# DC_Measure.net
KiCad netlist of a schematic drawn in Altium Designer
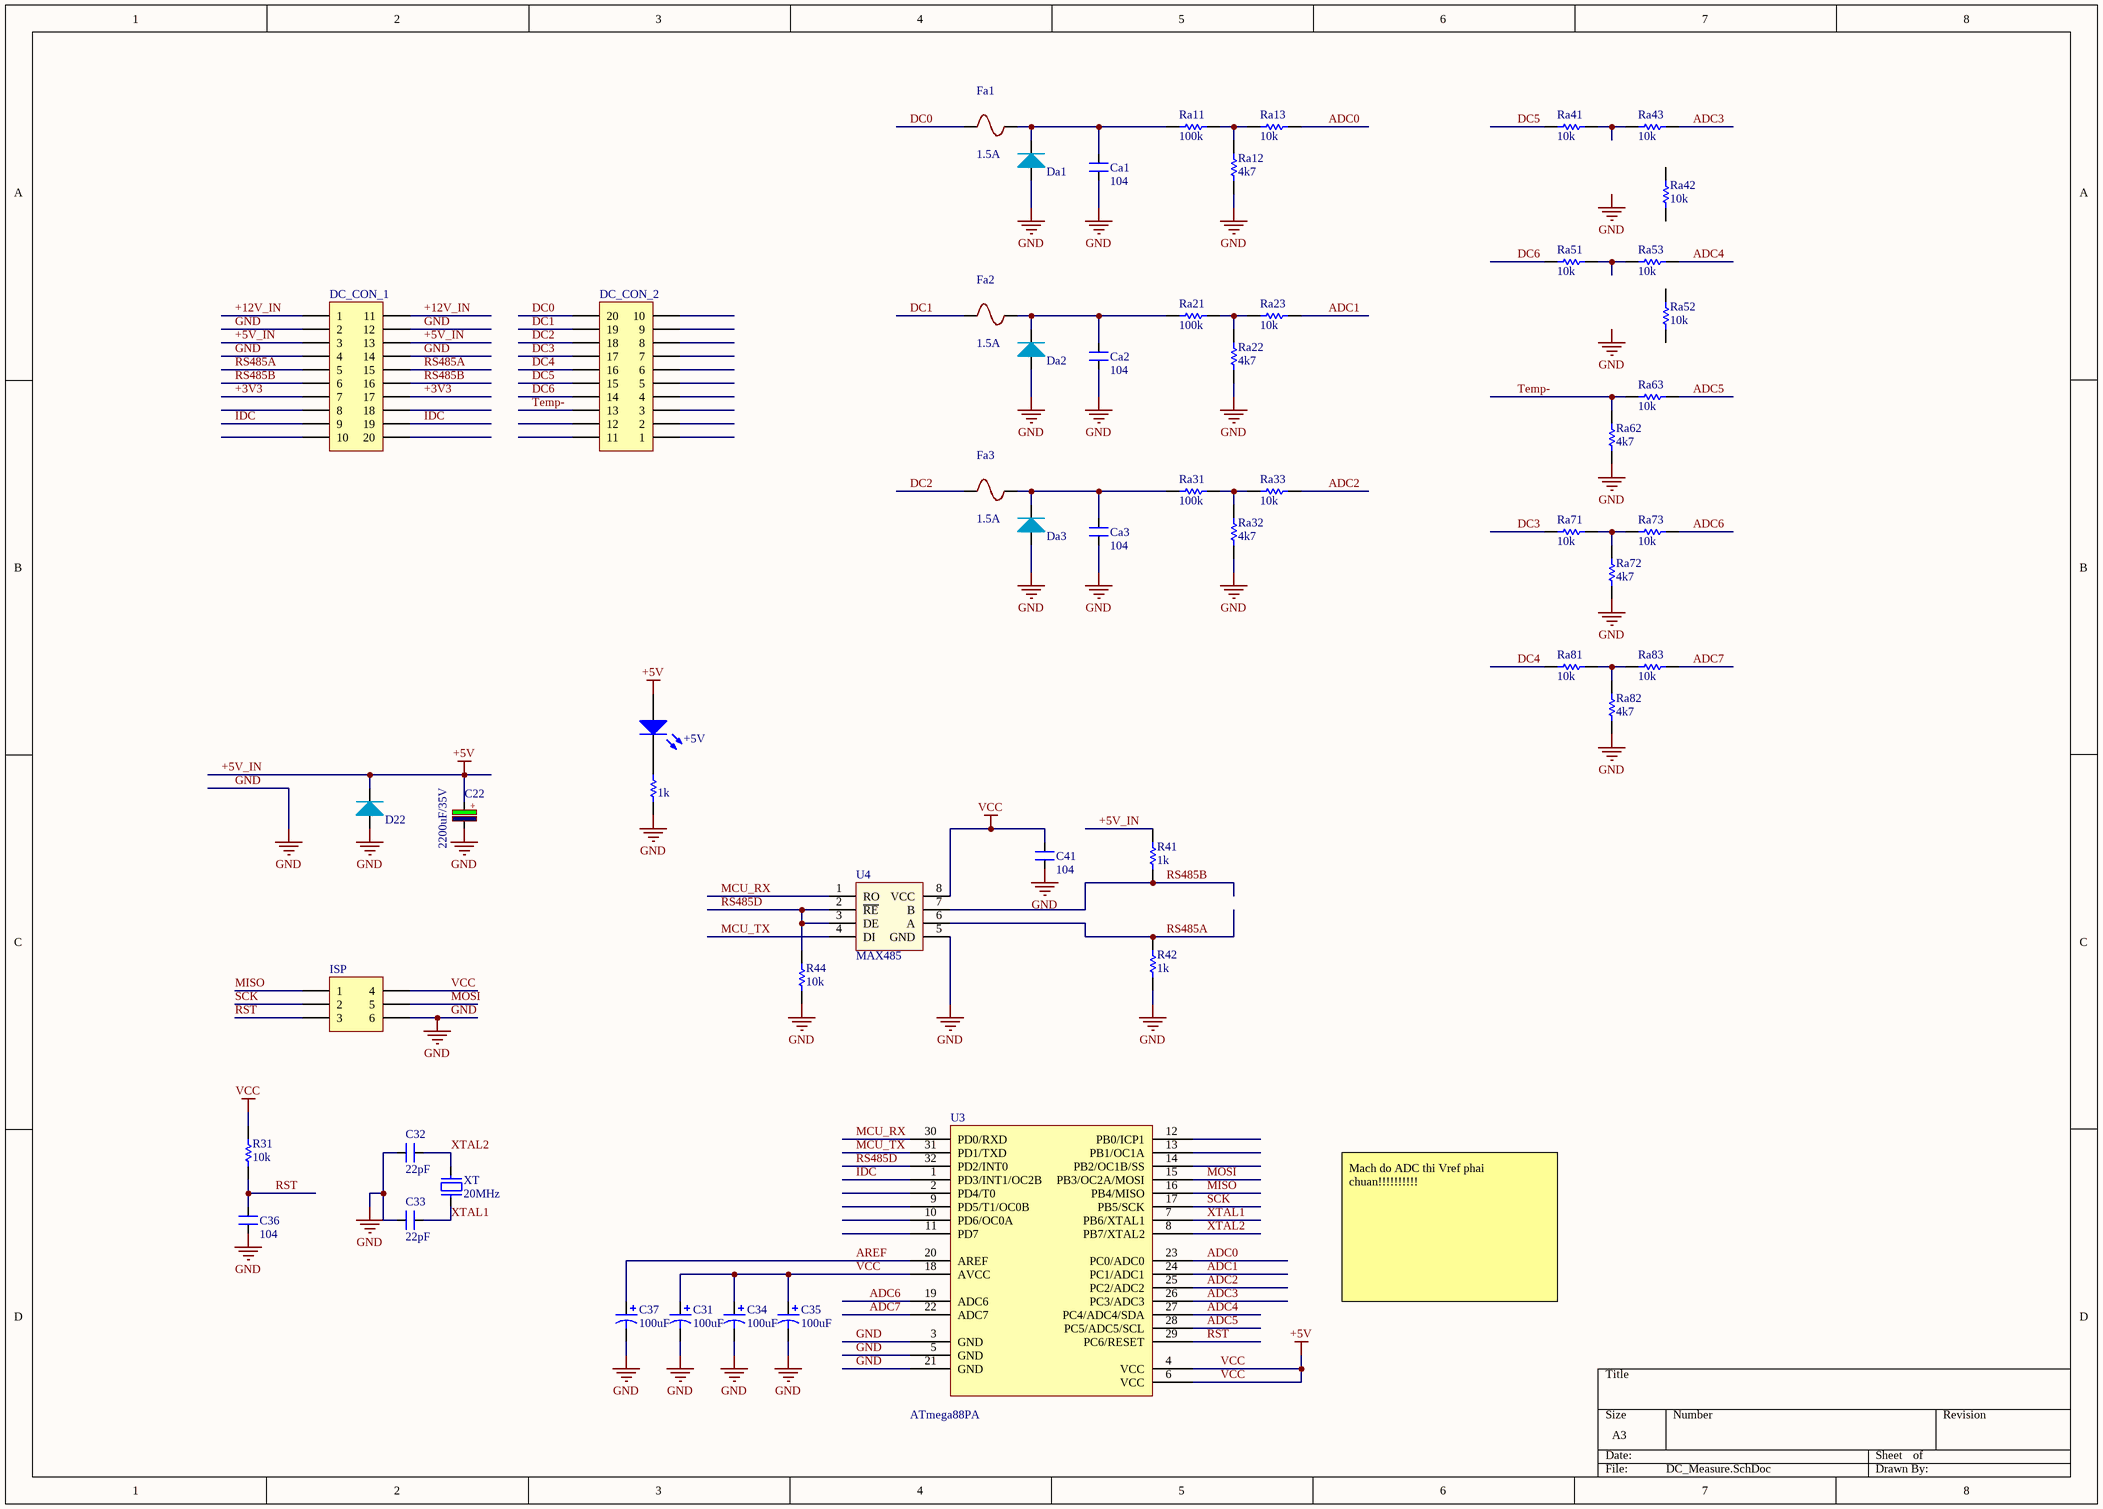
[diagram p0: DC_Measure.SchDoc]

(export (version "E")
  (design (tool "Eeschema 10.0.6"))
  (components
    (comp (ref "+5V") (value "Led") (footprint "LED 5mm RED") (libsource (lib "Tuan") (part "Led")))
    (comp (ref "C22")
      (value "2200uF/35V")
      (footprint "PBL - SMD Packages:CAP_ELEC_SIZE_G")
      (description "Cap 1000uF/16V - 220uF/50V")
      (libsource (lib "heromap") (part "CP4"))
    )
    (comp (ref "C31")
      (value "100uF")
      (footprint "CAPC2012N_F")
      (fields (field (name "Comment") "Cap"))
      (libsource (lib "Tuan") (part "Cap"))
    )
    (comp (ref "C32")
      (value "22pF")
      (footprint "CAPC1608N")
      (fields (field (name "Comment") "CAP NP"))
      (libsource (lib "Tuan") (part "CAP NP"))
    )
    (comp (ref "C33")
      (value "22pF")
      (footprint "CAPC1608N")
      (fields (field (name "Comment") "CAP NP"))
      (libsource (lib "Tuan") (part "CAP NP"))
    )
    (comp (ref "C34")
      (value "100uF")
      (footprint "CAPC2012N_F")
      (fields (field (name "Comment") "Cap"))
      (libsource (lib "Tuan") (part "Cap"))
    )
    (comp (ref "C35")
      (value "100uF")
      (footprint "CAPC2012N_F")
      (fields (field (name "Comment") "Cap"))
      (libsource (lib "Tuan") (part "Cap"))
    )
    (comp (ref "C36")
      (value "104")
      (footprint "CAPC1608N")
      (fields (field (name "Comment") "CAP NP"))
      (libsource (lib "Tuan") (part "CAP NP"))
    )
    (comp (ref "C37")
      (value "100uF")
      (footprint "CAPC2012N_F")
      (fields (field (name "Comment") "Cap"))
      (libsource (lib "Tuan") (part "Cap"))
    )
    (comp (ref "C41")
      (value "104")
      (footprint "CAPC2012N_F")
      (fields (field (name "Comment") "100nF/104"))
      (libsource (lib "Tuan") (part "CAP NP"))
    )
    (comp (ref "Ca1")
      (value "104")
      (footprint "CAPC2012N_F")
      (fields (field (name "Comment") "CAP NP"))
      (libsource (lib "Tuan") (part "CAP NP"))
    )
    (comp (ref "Ca2")
      (value "104")
      (footprint "CAPC2012N_F")
      (fields (field (name "Comment") "CAP NP"))
      (libsource (lib "Tuan") (part "CAP NP"))
    )
    (comp (ref "Ca3")
      (value "104")
      (footprint "CAPC2012N_F")
      (fields (field (name "Comment") "CAP NP"))
      (libsource (lib "Tuan") (part "CAP NP"))
    )
    (comp (ref "D22") (value "Diode") (footprint "DO-214AC") (libsource (lib "Tuan") (part "Diode")))
    (comp (ref "Da1") (value "Diode") (footprint "DO-214AC") (libsource (lib "Tuan") (part "Diode")))
    (comp (ref "Da2") (value "Diode") (footprint "DO-214AC") (libsource (lib "Tuan") (part "Diode")))
    (comp (ref "Da3") (value "Diode") (footprint "DO-214AC") (libsource (lib "Tuan") (part "Diode")))
    (comp (ref "DC_CON_1")
      (value "Header 10X2A")
      (footprint "OMC10")
      (description "Header, 10-Pin, Dual row")
      (fields (field (name "PUBLISHER") "Altium Limited"))
      (libsource (lib "") (part "Header 10X2A_1"))
    )
    (comp (ref "DC_CON_2")
      (value "Header 10X2A")
      (footprint "OMC10")
      (description "Header, 10-Pin, Dual row")
      (fields (field (name "PUBLISHER") "Altium Limited"))
      (libsource (lib "Miscellaneous Connectors") (part "Header 10X2A"))
    )
    (comp (ref "Fa1") (value "1.5A") (footprint "SMD 1206") (libsource (lib "Tuan") (part "Fuse")))
    (comp (ref "Fa2") (value "1.5A") (footprint "SMD 1206") (libsource (lib "Tuan") (part "Fuse")))
    (comp (ref "Fa3") (value "1.5A") (footprint "SMD 1206") (libsource (lib "Tuan") (part "Fuse")))
    (comp (ref "ISP")
      (value "Header 3X2A")
      (footprint "HDR2X3_CEN")
      (description "Header, 3-Pin, Dual row")
      (fields (field (name "PUBLISHER") "Altium Limited"))
      (libsource (lib "Miscellaneous Connectors") (part "Header 3X2A"))
    )
    (comp (ref "R22")
      (value "1k")
      (footprint "RESC2012N_F")
      (fields (field (name "Comment") "Res_0805_1k"))
      (libsource (lib "Tuan") (part "Res"))
    )
    (comp (ref "R31")
      (value "10k")
      (footprint "RESC1608N_ZERO")
      (fields (field (name "Comment") "Res"))
      (libsource (lib "Tuan") (part "Res"))
    )
    (comp (ref "R41")
      (value "1k")
      (footprint "RESC1608N_ZERO")
      (description "Tro dan")
      (libsource (lib "GPS_Clock_v12") (part "Res"))
    )
    (comp (ref "R42")
      (value "1k")
      (footprint "RESC1608N_ZERO")
      (description "Tro dan")
      (libsource (lib "GPS_Clock_v12") (part "Res"))
    )
    (comp (ref "R44")
      (value "10k")
      (footprint "RESC1608N_ZERO")
      (description "Tro dan")
      (fields (field (name "Comment") "330R"))
      (libsource (lib "GPS_Clock_v12") (part "Res"))
    )
    (comp (ref "Ra11")
      (value "100k")
      (footprint "RESC2012N_F")
      (fields (field (name "Comment") "Res"))
      (libsource (lib "Tuan") (part "Res"))
    )
    (comp (ref "Ra12")
      (value "4k7")
      (footprint "RESC2012N_F")
      (fields (field (name "Comment") "Res"))
      (libsource (lib "Tuan") (part "Res"))
    )
    (comp (ref "Ra13")
      (value "10k")
      (footprint "RESC2012N_F")
      (fields (field (name "Comment") "Res"))
      (libsource (lib "Tuan") (part "Res"))
    )
    (comp (ref "Ra21")
      (value "100k")
      (footprint "RESC2012N_F")
      (fields (field (name "Comment") "Res"))
      (libsource (lib "Tuan") (part "Res"))
    )
    (comp (ref "Ra22")
      (value "4k7")
      (footprint "RESC2012N_F")
      (fields (field (name "Comment") "Res"))
      (libsource (lib "Tuan") (part "Res"))
    )
    (comp (ref "Ra23")
      (value "10k")
      (footprint "RESC2012N_F")
      (fields (field (name "Comment") "Res"))
      (libsource (lib "Tuan") (part "Res"))
    )
    (comp (ref "Ra31")
      (value "100k")
      (footprint "RESC2012N_F")
      (fields (field (name "Comment") "Res"))
      (libsource (lib "Tuan") (part "Res"))
    )
    (comp (ref "Ra32")
      (value "4k7")
      (footprint "RESC2012N_F")
      (fields (field (name "Comment") "Res"))
      (libsource (lib "Tuan") (part "Res"))
    )
    (comp (ref "Ra33")
      (value "10k")
      (footprint "RESC2012N_F")
      (fields (field (name "Comment") "Res"))
      (libsource (lib "Tuan") (part "Res"))
    )
    (comp (ref "Ra41")
      (value "10k")
      (footprint "RESC2012N_F")
      (fields (field (name "Comment") "Res"))
      (libsource (lib "Tuan") (part "Res"))
    )
    (comp (ref "Ra42")
      (value "10k")
      (footprint "RESC2012N_F")
      (fields (field (name "Comment") "Res"))
      (libsource (lib "Tuan") (part "Res"))
    )
    (comp (ref "Ra43")
      (value "10k")
      (footprint "RESC2012N_F")
      (fields (field (name "Comment") "Res"))
      (libsource (lib "Tuan") (part "Res"))
    )
    (comp (ref "Ra51")
      (value "10k")
      (footprint "RESC2012N_F")
      (fields (field (name "Comment") "Res"))
      (libsource (lib "Tuan") (part "Res"))
    )
    (comp (ref "Ra52")
      (value "10k")
      (footprint "RESC2012N_F")
      (fields (field (name "Comment") "Res"))
      (libsource (lib "Tuan") (part "Res"))
    )
    (comp (ref "Ra53")
      (value "10k")
      (footprint "RESC2012N_F")
      (fields (field (name "Comment") "Res"))
      (libsource (lib "Tuan") (part "Res"))
    )
    (comp (ref "Ra62")
      (value "4k7")
      (footprint "RESC2012N_F")
      (fields (field (name "Comment") "Res"))
      (libsource (lib "Tuan") (part "Res"))
    )
    (comp (ref "Ra63")
      (value "10k")
      (footprint "RESC2012N_F")
      (fields (field (name "Comment") "Res"))
      (libsource (lib "Tuan") (part "Res"))
    )
    (comp (ref "Ra71")
      (value "10k")
      (footprint "RESC2012N_F")
      (fields (field (name "Comment") "Res"))
      (libsource (lib "Tuan") (part "Res"))
    )
    (comp (ref "Ra72")
      (value "4k7")
      (footprint "RESC2012N_F")
      (fields (field (name "Comment") "Res"))
      (libsource (lib "Tuan") (part "Res"))
    )
    (comp (ref "Ra73")
      (value "10k")
      (footprint "RESC2012N_F")
      (fields (field (name "Comment") "Res"))
      (libsource (lib "Tuan") (part "Res"))
    )
    (comp (ref "Ra81")
      (value "10k")
      (footprint "RESC2012N_F")
      (fields (field (name "Comment") "Res"))
      (libsource (lib "Tuan") (part "Res"))
    )
    (comp (ref "Ra82")
      (value "4k7")
      (footprint "RESC2012N_F")
      (fields (field (name "Comment") "Res"))
      (libsource (lib "Tuan") (part "Res"))
    )
    (comp (ref "Ra83")
      (value "10k")
      (footprint "RESC2012N_F")
      (fields (field (name "Comment") "Res"))
      (libsource (lib "Tuan") (part "Res"))
    )
    (comp (ref "U3")
      (value "ATmega88PA")
      (footprint "32PIN")
      (description "ATmega48/168/328")
      (libsource (lib "Tuan") (part "ATmega48/168/328"))
    )
    (comp (ref "U4")
      (value "MAX485")
      (footprint "SO-8")
      (description "RS232 - RS485 (Same sn75176)")
      (libsource (lib "heromap") (part "MAX485"))
    )
    (comp (ref "XT") (value "20MHz") (footprint "XT2") (libsource (lib "Tuan") (part "Crystal")))
  )
  (nets
    (net (code "1") (name "+5V") (class "Default")
      (node (ref "+5V") (pin "1") (pinfunction "A_1") (pintype "passive"))
      (node (ref "C22") (pin "1") (pinfunction "1_1") (pintype "passive"))
      (node (ref "C31") (pin "1") (pinfunction "1_1") (pintype "passive"))
      (node (ref "C34") (pin "1") (pinfunction "1_1") (pintype "passive"))
      (node (ref "C35") (pin "1") (pinfunction "1_1") (pintype "passive"))
      (node (ref "C41") (pin "2") (pinfunction "2_2") (pintype "passive"))
      (node (ref "D22") (pin "2") (pinfunction "K_2") (pintype "passive"))
      (node (ref "DC_CON_1") (pin "13") (pinfunction "13_13") (pintype "passive"))
      (node (ref "DC_CON_1") (pin "3") (pinfunction "3_3") (pintype "passive"))
      (node (ref "ISP") (pin "4") (pinfunction "4_4") (pintype "passive"))
      (node (ref "R31") (pin "2") (pinfunction "2_2") (pintype "passive"))
      (node (ref "R41") (pin "2") (pinfunction "2_2") (pintype "passive"))
      (node (ref "U3") (pin "18") (pinfunction "AVCC_18") (pintype "passive"))
      (node (ref "U3") (pin "4") (pinfunction "VCC_4") (pintype "passive"))
      (node (ref "U3") (pin "6") (pinfunction "VCC_6") (pintype "passive"))
      (node (ref "U4") (pin "8") (pinfunction "VCC_8") (pintype "passive"))
    )
    (net (code "2") (name "/+3V3") (class "Default")
      (node (ref "DC_CON_1") (pin "17") (pinfunction "17_17") (pintype "passive"))
      (node (ref "DC_CON_1") (pin "7") (pinfunction "7_7") (pintype "passive"))
    )
    (net (code "3") (name "/+12V_IN") (class "Default")
      (node (ref "DC_CON_1") (pin "1") (pinfunction "1_1") (pintype "passive"))
      (node (ref "DC_CON_1") (pin "11") (pinfunction "11_11") (pintype "passive"))
    )
    (net (code "4") (name "/ADC0") (class "Default")
      (node (ref "Ra13") (pin "1") (pinfunction "1_1") (pintype "passive"))
      (node (ref "U3") (pin "23") (pinfunction "PC0/ADC0_23") (pintype "passive"))
    )
    (net (code "5") (name "/ADC1") (class "Default")
      (node (ref "Ra23") (pin "2") (pinfunction "2_2") (pintype "passive"))
      (node (ref "U3") (pin "24") (pinfunction "PC1/ADC1_24") (pintype "passive"))
    )
    (net (code "6") (name "/ADC2") (class "Default")
      (node (ref "Ra33") (pin "1") (pinfunction "1_1") (pintype "passive"))
      (node (ref "U3") (pin "25") (pinfunction "PC2/ADC2_25") (pintype "passive"))
    )
    (net (code "7") (name "/ADC3") (class "Default")
      (node (ref "Ra43") (pin "1") (pinfunction "1_1") (pintype "passive"))
      (node (ref "U3") (pin "26") (pinfunction "PC3/ADC3_26") (pintype "passive"))
    )
    (net (code "8") (name "/ADC4") (class "Default")
      (node (ref "Ra53") (pin "2") (pinfunction "2_2") (pintype "passive"))
      (node (ref "U3") (pin "27") (pinfunction "PC4/ADC4/SDA_27") (pintype "passive"))
    )
    (net (code "9") (name "/ADC5") (class "Default")
      (node (ref "Ra63") (pin "1") (pinfunction "1_1") (pintype "passive"))
      (node (ref "U3") (pin "28") (pinfunction "PC5/ADC5/SCL_28") (pintype "passive"))
    )
    (net (code "10") (name "/ADC6") (class "Default")
      (node (ref "Ra73") (pin "2") (pinfunction "2_2") (pintype "passive"))
      (node (ref "U3") (pin "19") (pinfunction "ADC6_19") (pintype "passive"))
    )
    (net (code "11") (name "/ADC7") (class "Default")
      (node (ref "Ra83") (pin "2") (pinfunction "2_2") (pintype "passive"))
      (node (ref "U3") (pin "22") (pinfunction "ADC7_22") (pintype "passive"))
    )
    (net (code "12") (name "/AREF") (class "Default")
      (node (ref "C37") (pin "1") (pinfunction "1_1") (pintype "passive"))
      (node (ref "U3") (pin "20") (pinfunction "AREF_20") (pintype "passive"))
    )
    (net (code "13") (name "/DC0") (class "Default")
      (node (ref "DC_CON_2") (pin "20") (pinfunction "20_20") (pintype "passive"))
      (node (ref "Fa1") (pin "1") (pinfunction "1_1") (pintype "passive"))
    )
    (net (code "14") (name "/DC1") (class "Default")
      (node (ref "DC_CON_2") (pin "19") (pinfunction "19_19") (pintype "passive"))
      (node (ref "Fa2") (pin "1") (pinfunction "1_1") (pintype "passive"))
    )
    (net (code "15") (name "/DC2") (class "Default")
      (node (ref "DC_CON_2") (pin "18") (pinfunction "18_18") (pintype "passive"))
      (node (ref "Fa3") (pin "1") (pinfunction "1_1") (pintype "passive"))
    )
    (net (code "16") (name "/DC3") (class "Default")
      (node (ref "DC_CON_2") (pin "17") (pinfunction "17_17") (pintype "passive"))
      (node (ref "Ra71") (pin "2") (pinfunction "2_2") (pintype "passive"))
    )
    (net (code "17") (name "/DC4") (class "Default")
      (node (ref "DC_CON_2") (pin "16") (pinfunction "16_16") (pintype "passive"))
      (node (ref "Ra81") (pin "2") (pinfunction "2_2") (pintype "passive"))
    )
    (net (code "18") (name "/DC5") (class "Default")
      (node (ref "DC_CON_2") (pin "15") (pinfunction "15_15") (pintype "passive"))
      (node (ref "Ra41") (pin "1") (pinfunction "1_1") (pintype "passive"))
    )
    (net (code "19") (name "/DC6") (class "Default")
      (node (ref "DC_CON_2") (pin "14") (pinfunction "14_14") (pintype "passive"))
      (node (ref "Ra51") (pin "2") (pinfunction "2_2") (pintype "passive"))
    )
    (net (code "20") (name "/IDC") (class "Default")
      (node (ref "DC_CON_1") (pin "19") (pinfunction "19_19") (pintype "passive"))
      (node (ref "DC_CON_1") (pin "9") (pinfunction "9_9") (pintype "passive"))
      (node (ref "U3") (pin "1") (pinfunction "PD3/INT1/OC2B_1") (pintype "passive"))
    )
    (net (code "21") (name "/MCU_RX") (class "Default")
      (node (ref "U3") (pin "30") (pinfunction "PD0/RXD_30") (pintype "passive"))
      (node (ref "U4") (pin "1") (pinfunction "RO_1") (pintype "passive"))
    )
    (net (code "22") (name "/MCU_TX") (class "Default")
      (node (ref "U3") (pin "31") (pinfunction "PD1/TXD_31") (pintype "passive"))
      (node (ref "U4") (pin "4") (pinfunction "DI_4") (pintype "passive"))
    )
    (net (code "23") (name "/MISO") (class "Default")
      (node (ref "ISP") (pin "1") (pinfunction "1_1") (pintype "passive"))
      (node (ref "U3") (pin "16") (pinfunction "PB4/MISO_16") (pintype "passive"))
    )
    (net (code "24") (name "/MOSI") (class "Default")
      (node (ref "ISP") (pin "5") (pinfunction "5_5") (pintype "passive"))
      (node (ref "U3") (pin "15") (pinfunction "PB3/OC2A/MOSI_15") (pintype "passive"))
    )
    (net (code "25") (name "/RS485A") (class "Default")
      (node (ref "DC_CON_1") (pin "15") (pinfunction "15_15") (pintype "passive"))
      (node (ref "DC_CON_1") (pin "5") (pinfunction "5_5") (pintype "passive"))
      (node (ref "R42") (pin "2") (pinfunction "2_2") (pintype "passive"))
      (node (ref "U4") (pin "6") (pinfunction "A_6") (pintype "passive"))
    )
    (net (code "26") (name "/RS485B") (class "Default")
      (node (ref "DC_CON_1") (pin "16") (pinfunction "16_16") (pintype "passive"))
      (node (ref "DC_CON_1") (pin "6") (pinfunction "6_6") (pintype "passive"))
      (node (ref "R41") (pin "1") (pinfunction "1_1") (pintype "passive"))
      (node (ref "U4") (pin "7") (pinfunction "B_7") (pintype "passive"))
    )
    (net (code "27") (name "/RS485D") (class "Default")
      (node (ref "R44") (pin "2") (pinfunction "2_2") (pintype "passive"))
      (node (ref "U3") (pin "32") (pinfunction "PD2/INT0_32") (pintype "passive"))
      (node (ref "U4") (pin "2") (pinfunction "~{RE}_2") (pintype "passive"))
      (node (ref "U4") (pin "3") (pinfunction "DE_3") (pintype "passive"))
    )
    (net (code "28") (name "/RST") (class "Default")
      (node (ref "C36") (pin "2") (pinfunction "2_2") (pintype "passive"))
      (node (ref "ISP") (pin "3") (pinfunction "3_3") (pintype "passive"))
      (node (ref "R31") (pin "1") (pinfunction "1_1") (pintype "passive"))
      (node (ref "U3") (pin "29") (pinfunction "PC6/RESET_29") (pintype "passive"))
    )
    (net (code "29") (name "/SCK") (class "Default")
      (node (ref "ISP") (pin "2") (pinfunction "2_2") (pintype "passive"))
      (node (ref "U3") (pin "17") (pinfunction "PB5/SCK_17") (pintype "passive"))
    )
    (net (code "30") (name "/Temp-") (class "Default")
      (node (ref "DC_CON_2") (pin "13") (pinfunction "13_13") (pintype "passive"))
      (node (ref "Ra62") (pin "2") (pinfunction "2_2") (pintype "passive"))
      (node (ref "Ra63") (pin "2") (pinfunction "2_2") (pintype "passive"))
    )
    (net (code "31") (name "/XTAL1") (class "Default")
      (node (ref "C33") (pin "1") (pinfunction "1_1") (pintype "passive"))
      (node (ref "U3") (pin "7") (pinfunction "PB6/XTAL1_7") (pintype "passive"))
      (node (ref "XT") (pin "1") (pinfunction "1_1") (pintype "passive"))
    )
    (net (code "32") (name "/XTAL2") (class "Default")
      (node (ref "C32") (pin "1") (pinfunction "1_1") (pintype "passive"))
      (node (ref "U3") (pin "8") (pinfunction "PB7/XTAL2_8") (pintype "passive"))
      (node (ref "XT") (pin "2") (pinfunction "2_2") (pintype "passive"))
    )
    (net (code "33") (name "GND") (class "Default")
      (node (ref "C22") (pin "2") (pinfunction "2_2") (pintype "passive"))
      (node (ref "C31") (pin "2") (pinfunction "2_2") (pintype "passive"))
      (node (ref "C32") (pin "2") (pinfunction "2_2") (pintype "passive"))
      (node (ref "C33") (pin "2") (pinfunction "2_2") (pintype "passive"))
      (node (ref "C34") (pin "2") (pinfunction "2_2") (pintype "passive"))
      (node (ref "C35") (pin "2") (pinfunction "2_2") (pintype "passive"))
      (node (ref "C36") (pin "1") (pinfunction "1_1") (pintype "passive"))
      (node (ref "C37") (pin "2") (pinfunction "2_2") (pintype "passive"))
      (node (ref "C41") (pin "1") (pinfunction "1_1") (pintype "passive"))
      (node (ref "Ca1") (pin "1") (pinfunction "1_1") (pintype "passive"))
      (node (ref "Ca2") (pin "1") (pinfunction "1_1") (pintype "passive"))
      (node (ref "Ca3") (pin "1") (pinfunction "1_1") (pintype "passive"))
      (node (ref "D22") (pin "1") (pinfunction "A_1") (pintype "passive"))
      (node (ref "DC_CON_1") (pin "12") (pinfunction "12_12") (pintype "passive"))
      (node (ref "DC_CON_1") (pin "14") (pinfunction "14_14") (pintype "passive"))
      (node (ref "DC_CON_1") (pin "2") (pinfunction "2_2") (pintype "passive"))
      (node (ref "DC_CON_1") (pin "4") (pinfunction "4_4") (pintype "passive"))
      (node (ref "Da1") (pin "1") (pinfunction "A_1") (pintype "passive"))
      (node (ref "Da2") (pin "1") (pinfunction "A_1") (pintype "passive"))
      (node (ref "Da3") (pin "1") (pinfunction "A_1") (pintype "passive"))
      (node (ref "ISP") (pin "6") (pinfunction "6_6") (pintype "passive"))
      (node (ref "R22") (pin "2") (pinfunction "2_2") (pintype "passive"))
      (node (ref "R42") (pin "1") (pinfunction "1_1") (pintype "passive"))
      (node (ref "R44") (pin "1") (pinfunction "1_1") (pintype "passive"))
      (node (ref "Ra12") (pin "1") (pinfunction "1_1") (pintype "passive"))
      (node (ref "Ra22") (pin "2") (pinfunction "2_2") (pintype "passive"))
      (node (ref "Ra32") (pin "1") (pinfunction "1_1") (pintype "passive"))
      (node (ref "Ra62") (pin "1") (pinfunction "1_1") (pintype "passive"))
      (node (ref "Ra72") (pin "2") (pinfunction "2_2") (pintype "passive"))
      (node (ref "Ra82") (pin "2") (pinfunction "2_2") (pintype "passive"))
      (node (ref "U3") (pin "21") (pinfunction "GND_21") (pintype "power_in"))
      (node (ref "U3") (pin "3") (pinfunction "GND_3") (pintype "power_in"))
      (node (ref "U3") (pin "5") (pinfunction "GND_5") (pintype "power_in"))
      (node (ref "U4") (pin "5") (pinfunction "GND_5") (pintype "passive"))
    )
    (net (code "34") (name "Net-(+5V-K)") (class "Default")
      (node (ref "+5V") (pin "2") (pinfunction "K_2") (pintype "passive"))
      (node (ref "R22") (pin "1") (pinfunction "1_1") (pintype "passive"))
    )
    (net (code "35") (name "Net-(Da1-K)") (class "Default")
      (node (ref "Ca1") (pin "2") (pinfunction "2_2") (pintype "passive"))
      (node (ref "Da1") (pin "2") (pinfunction "K_2") (pintype "passive"))
      (node (ref "Fa1") (pin "2") (pinfunction "2_2") (pintype "passive"))
      (node (ref "Ra11") (pin "1") (pinfunction "1_1") (pintype "passive"))
    )
    (net (code "36") (name "Net-(Da2-K)") (class "Default")
      (node (ref "Ca2") (pin "2") (pinfunction "2_2") (pintype "passive"))
      (node (ref "Da2") (pin "2") (pinfunction "K_2") (pintype "passive"))
      (node (ref "Fa2") (pin "2") (pinfunction "2_2") (pintype "passive"))
      (node (ref "Ra21") (pin "2") (pinfunction "2_2") (pintype "passive"))
    )
    (net (code "37") (name "Net-(Da3-K)") (class "Default")
      (node (ref "Ca3") (pin "2") (pinfunction "2_2") (pintype "passive"))
      (node (ref "Da3") (pin "2") (pinfunction "K_2") (pintype "passive"))
      (node (ref "Fa3") (pin "2") (pinfunction "2_2") (pintype "passive"))
      (node (ref "Ra31") (pin "1") (pinfunction "1_1") (pintype "passive"))
    )
    (net (code "38") (name "Net-(Ra11-Pad2)") (class "Default")
      (node (ref "Ra11") (pin "2") (pinfunction "2_2") (pintype "passive"))
      (node (ref "Ra12") (pin "2") (pinfunction "2_2") (pintype "passive"))
      (node (ref "Ra13") (pin "2") (pinfunction "2_2") (pintype "passive"))
    )
    (net (code "39") (name "Net-(Ra21-Pad1)") (class "Default")
      (node (ref "Ra21") (pin "1") (pinfunction "1_1") (pintype "passive"))
      (node (ref "Ra22") (pin "1") (pinfunction "1_1") (pintype "passive"))
      (node (ref "Ra23") (pin "1") (pinfunction "1_1") (pintype "passive"))
    )
    (net (code "40") (name "Net-(Ra31-Pad2)") (class "Default")
      (node (ref "Ra31") (pin "2") (pinfunction "2_2") (pintype "passive"))
      (node (ref "Ra32") (pin "2") (pinfunction "2_2") (pintype "passive"))
      (node (ref "Ra33") (pin "2") (pinfunction "2_2") (pintype "passive"))
    )
    (net (code "41") (name "Net-(Ra41-Pad2)") (class "Default")
      (node (ref "Ra41") (pin "2") (pinfunction "2_2") (pintype "passive"))
      (node (ref "Ra43") (pin "2") (pinfunction "2_2") (pintype "passive"))
    )
    (net (code "42") (name "Net-(Ra51-Pad1)") (class "Default")
      (node (ref "Ra51") (pin "1") (pinfunction "1_1") (pintype "passive"))
      (node (ref "Ra53") (pin "1") (pinfunction "1_1") (pintype "passive"))
    )
    (net (code "43") (name "Net-(Ra71-Pad1)") (class "Default")
      (node (ref "Ra71") (pin "1") (pinfunction "1_1") (pintype "passive"))
      (node (ref "Ra72") (pin "1") (pinfunction "1_1") (pintype "passive"))
      (node (ref "Ra73") (pin "1") (pinfunction "1_1") (pintype "passive"))
    )
    (net (code "44") (name "Net-(Ra81-Pad1)") (class "Default")
      (node (ref "Ra81") (pin "1") (pinfunction "1_1") (pintype "passive"))
      (node (ref "Ra82") (pin "1") (pinfunction "1_1") (pintype "passive"))
      (node (ref "Ra83") (pin "1") (pinfunction "1_1") (pintype "passive"))
    )
    (net (code "45") (name "unconnected-(DC_CON_1-Pad8)") (class "Default")
      (node (ref "DC_CON_1") (pin "8") (pinfunction "8_8") (pintype "passive"))
    )
    (net (code "46") (name "unconnected-(DC_CON_1-Pad10)") (class "Default")
      (node (ref "DC_CON_1") (pin "10") (pinfunction "10_10") (pintype "passive"))
    )
    (net (code "47") (name "unconnected-(DC_CON_1-Pad18)") (class "Default")
      (node (ref "DC_CON_1") (pin "18") (pinfunction "18_18") (pintype "passive"))
    )
    (net (code "48") (name "unconnected-(DC_CON_1-Pad20)") (class "Default")
      (node (ref "DC_CON_1") (pin "20") (pinfunction "20_20") (pintype "passive"))
    )
    (net (code "49") (name "unconnected-(DC_CON_2-Pad1)") (class "Default")
      (node (ref "DC_CON_2") (pin "1") (pinfunction "1_1") (pintype "passive"))
    )
    (net (code "50") (name "unconnected-(DC_CON_2-Pad2)") (class "Default")
      (node (ref "DC_CON_2") (pin "2") (pinfunction "2_2") (pintype "passive"))
    )
    (net (code "51") (name "unconnected-(DC_CON_2-Pad3)") (class "Default")
      (node (ref "DC_CON_2") (pin "3") (pinfunction "3_3") (pintype "passive"))
    )
    (net (code "52") (name "unconnected-(DC_CON_2-Pad4)") (class "Default")
      (node (ref "DC_CON_2") (pin "4") (pinfunction "4_4") (pintype "passive"))
    )
    (net (code "53") (name "unconnected-(DC_CON_2-Pad5)") (class "Default")
      (node (ref "DC_CON_2") (pin "5") (pinfunction "5_5") (pintype "passive"))
    )
    (net (code "54") (name "unconnected-(DC_CON_2-Pad6)") (class "Default")
      (node (ref "DC_CON_2") (pin "6") (pinfunction "6_6") (pintype "passive"))
    )
    (net (code "55") (name "unconnected-(DC_CON_2-Pad7)") (class "Default")
      (node (ref "DC_CON_2") (pin "7") (pinfunction "7_7") (pintype "passive"))
    )
    (net (code "56") (name "unconnected-(DC_CON_2-Pad8)") (class "Default")
      (node (ref "DC_CON_2") (pin "8") (pinfunction "8_8") (pintype "passive"))
    )
    (net (code "57") (name "unconnected-(DC_CON_2-Pad9)") (class "Default")
      (node (ref "DC_CON_2") (pin "9") (pinfunction "9_9") (pintype "passive"))
    )
    (net (code "58") (name "unconnected-(DC_CON_2-Pad10)") (class "Default")
      (node (ref "DC_CON_2") (pin "10") (pinfunction "10_10") (pintype "passive"))
    )
    (net (code "59") (name "unconnected-(DC_CON_2-Pad11)") (class "Default")
      (node (ref "DC_CON_2") (pin "11") (pinfunction "11_11") (pintype "passive"))
    )
    (net (code "60") (name "unconnected-(DC_CON_2-Pad12)") (class "Default")
      (node (ref "DC_CON_2") (pin "12") (pinfunction "12_12") (pintype "passive"))
    )
    (net (code "61") (name "unconnected-(Ra42-Pad1)") (class "Default")
      (node (ref "Ra42") (pin "1") (pinfunction "1_1") (pintype "passive"))
    )
    (net (code "62") (name "unconnected-(Ra42-Pad2)") (class "Default")
      (node (ref "Ra42") (pin "2") (pinfunction "2_2") (pintype "passive"))
    )
    (net (code "63") (name "unconnected-(Ra52-Pad1)") (class "Default")
      (node (ref "Ra52") (pin "1") (pinfunction "1_1") (pintype "passive"))
    )
    (net (code "64") (name "unconnected-(Ra52-Pad2)") (class "Default")
      (node (ref "Ra52") (pin "2") (pinfunction "2_2") (pintype "passive"))
    )
    (net (code "65") (name "unconnected-(U3-PB0{slash}ICP1-Pad12)") (class "Default")
      (node (ref "U3") (pin "12") (pinfunction "PB0/ICP1_12") (pintype "passive"))
    )
    (net (code "66") (name "unconnected-(U3-PB1{slash}OC1A-Pad13)") (class "Default")
      (node (ref "U3") (pin "13") (pinfunction "PB1/OC1A_13") (pintype "passive"))
    )
    (net (code "67") (name "unconnected-(U3-PB2{slash}OC1B{slash}SS-Pad14)") (class "Default")
      (node (ref "U3") (pin "14") (pinfunction "PB2/OC1B/SS_14") (pintype "passive"))
    )
    (net (code "68") (name "unconnected-(U3-PD4{slash}T0-Pad2)") (class "Default")
      (node (ref "U3") (pin "2") (pinfunction "PD4/T0_2") (pintype "passive"))
    )
    (net (code "69") (name "unconnected-(U3-PD5{slash}T1{slash}OC0B-Pad9)") (class "Default")
      (node (ref "U3") (pin "9") (pinfunction "PD5/T1/OC0B_9") (pintype "passive"))
    )
    (net (code "70") (name "unconnected-(U3-PD6{slash}OC0A-Pad10)") (class "Default")
      (node (ref "U3") (pin "10") (pinfunction "PD6/OC0A_10") (pintype "passive"))
    )
    (net (code "71") (name "unconnected-(U3-PD7-Pad11)") (class "Default")
      (node (ref "U3") (pin "11") (pinfunction "PD7_11") (pintype "passive"))
    )
  )
)
